# LCD_BOARD.net
KiCad netlist of a schematic drawn in EAGLE
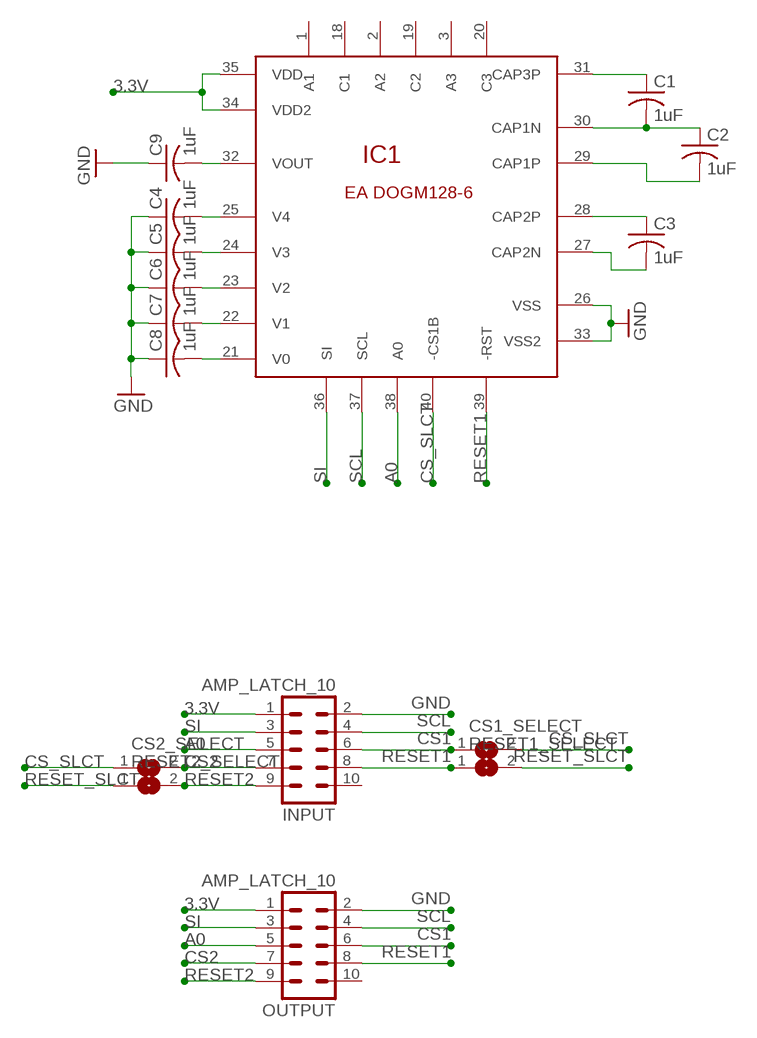
[diagram p0: schematic, sheet 1]

(export (version "E")
  (design (tool "Eeschema 10.0.6"))
  (components
    (comp (ref "C1")
      (value "1uF")
      (footprint "eagle-import:C1206")
      (libsource (lib "eagle-import") (part "C-USC1206"))
    )
    (comp (ref "C2")
      (value "1uF")
      (footprint "eagle-import:C1206")
      (libsource (lib "eagle-import") (part "C-USC1206"))
    )
    (comp (ref "C3")
      (value "1uF")
      (footprint "eagle-import:C1206")
      (libsource (lib "eagle-import") (part "C-USC1206"))
    )
    (comp (ref "C4")
      (value "1uF")
      (footprint "eagle-import:C1206")
      (libsource (lib "eagle-import") (part "C-USC1206"))
    )
    (comp (ref "C5")
      (value "1uF")
      (footprint "eagle-import:C1206")
      (libsource (lib "eagle-import") (part "C-USC1206"))
    )
    (comp (ref "C6")
      (value "1uF")
      (footprint "eagle-import:C1206")
      (libsource (lib "eagle-import") (part "C-USC1206"))
    )
    (comp (ref "C7")
      (value "1uF")
      (footprint "eagle-import:C1206")
      (libsource (lib "eagle-import") (part "C-USC1206"))
    )
    (comp (ref "C8")
      (value "1uF")
      (footprint "eagle-import:C1206")
      (libsource (lib "eagle-import") (part "C-USC1206"))
    )
    (comp (ref "C9")
      (value "1uF")
      (footprint "eagle-import:C1206")
      (libsource (lib "eagle-import") (part "C-USC1206"))
    )
    (comp (ref "CS1_SELECT")
      (value "SJ")
      (footprint "eagle-import:SJ")
      (libsource (lib "eagle-import") (part "SJ"))
    )
    (comp (ref "CS2_SELECT")
      (value "SJ")
      (footprint "eagle-import:SJ")
      (libsource (lib "eagle-import") (part "SJ"))
    )
    (comp (ref "IC1")
      (value "EADOGM128")
      (footprint "eagle-import:EADOGM128")
      (libsource (lib "eagle-import") (part "EADOGM128"))
    )
    (comp (ref "INPUT")
      (value "AMP_LATCH_10")
      (footprint "eagle-import:MA05-2")
      (fields (field (name "PART_NUM") "5499922-1"))
      (libsource (lib "eagle-import") (part "AMP_LATCH_10"))
    )
    (comp (ref "OUTPUT")
      (value "AMP_LATCH_10")
      (footprint "eagle-import:MA05-2")
      (fields (field (name "PART_NUM") "5499922-1"))
      (libsource (lib "eagle-import") (part "AMP_LATCH_10"))
    )
    (comp (ref "RESET1_SELECT")
      (value "SJ")
      (footprint "eagle-import:SJ")
      (libsource (lib "eagle-import") (part "SJ"))
    )
    (comp (ref "RESET2_SELECT")
      (value "SJ")
      (footprint "eagle-import:SJ")
      (libsource (lib "eagle-import") (part "SJ"))
    )
  )
  (nets
    (net (code "1") (name "/3.3V") (class "Default")
      (node (ref "IC1") (pin "34") (pinfunction "VDD2_34") (pintype "power_in"))
      (node (ref "IC1") (pin "35") (pinfunction "VDD_35") (pintype "power_in"))
      (node (ref "INPUT") (pin "1") (pinfunction "1_1") (pintype "passive"))
      (node (ref "OUTPUT") (pin "1") (pinfunction "1_1") (pintype "passive"))
    )
    (net (code "2") (name "/A0") (class "Default")
      (node (ref "IC1") (pin "38") (pinfunction "A0_38") (pintype "input"))
      (node (ref "INPUT") (pin "5") (pinfunction "5_5") (pintype "passive"))
      (node (ref "OUTPUT") (pin "5") (pinfunction "5_5") (pintype "passive"))
    )
    (net (code "3") (name "/CS1") (class "Default")
      (node (ref "CS1_SELECT") (pin "1") (pinfunction "1_1") (pintype "passive"))
      (node (ref "INPUT") (pin "6") (pinfunction "6_6") (pintype "passive"))
      (node (ref "OUTPUT") (pin "6") (pinfunction "6_6") (pintype "passive"))
    )
    (net (code "4") (name "/CS2") (class "Default")
      (node (ref "CS2_SELECT") (pin "2") (pinfunction "2_2") (pintype "passive"))
      (node (ref "INPUT") (pin "7") (pinfunction "7_7") (pintype "passive"))
      (node (ref "OUTPUT") (pin "7") (pinfunction "7_7") (pintype "passive"))
    )
    (net (code "5") (name "/CS_SLCT") (class "Default")
      (node (ref "CS1_SELECT") (pin "2") (pinfunction "2_2") (pintype "passive"))
      (node (ref "CS2_SELECT") (pin "1") (pinfunction "1_1") (pintype "passive"))
      (node (ref "IC1") (pin "40") (pinfunction "-CS1B_40") (pintype "input"))
    )
    (net (code "6") (name "/RESET1") (class "Default")
      (node (ref "IC1") (pin "39") (pinfunction "-RST_39") (pintype "input"))
      (node (ref "INPUT") (pin "8") (pinfunction "8_8") (pintype "passive"))
      (node (ref "OUTPUT") (pin "8") (pinfunction "8_8") (pintype "passive"))
      (node (ref "RESET1_SELECT") (pin "1") (pinfunction "1_1") (pintype "passive"))
    )
    (net (code "7") (name "/RESET2") (class "Default")
      (node (ref "INPUT") (pin "9") (pinfunction "9_9") (pintype "passive"))
      (node (ref "OUTPUT") (pin "9") (pinfunction "9_9") (pintype "passive"))
      (node (ref "RESET2_SELECT") (pin "2") (pinfunction "2_2") (pintype "passive"))
    )
    (net (code "8") (name "/RESET_SLCT") (class "Default")
      (node (ref "RESET1_SELECT") (pin "2") (pinfunction "2_2") (pintype "passive"))
      (node (ref "RESET2_SELECT") (pin "1") (pinfunction "1_1") (pintype "passive"))
    )
    (net (code "9") (name "/SCL") (class "Default")
      (node (ref "IC1") (pin "37") (pinfunction "SCL_37") (pintype "input"))
      (node (ref "INPUT") (pin "4") (pinfunction "4_4") (pintype "passive"))
      (node (ref "OUTPUT") (pin "4") (pinfunction "4_4") (pintype "passive"))
    )
    (net (code "10") (name "/SI") (class "Default")
      (node (ref "IC1") (pin "36") (pinfunction "SI_36") (pintype "input"))
      (node (ref "INPUT") (pin "3") (pinfunction "3_3") (pintype "passive"))
      (node (ref "OUTPUT") (pin "3") (pinfunction "3_3") (pintype "passive"))
    )
    (net (code "11") (name "GND") (class "Default")
      (node (ref "C4") (pin "1") (pinfunction "1_1") (pintype "passive"))
      (node (ref "C5") (pin "1") (pinfunction "1_1") (pintype "passive"))
      (node (ref "C6") (pin "1") (pinfunction "1_1") (pintype "passive"))
      (node (ref "C7") (pin "1") (pinfunction "1_1") (pintype "passive"))
      (node (ref "C8") (pin "1") (pinfunction "1_1") (pintype "passive"))
      (node (ref "C9") (pin "1") (pinfunction "1_1") (pintype "passive"))
      (node (ref "IC1") (pin "26") (pinfunction "VSS_26") (pintype "power_in"))
      (node (ref "IC1") (pin "33") (pinfunction "VSS2_33") (pintype "power_in"))
      (node (ref "INPUT") (pin "2") (pinfunction "2_2") (pintype "passive"))
      (node (ref "OUTPUT") (pin "2") (pinfunction "2_2") (pintype "passive"))
    )
    (net (code "12") (name "Net-(IC1-CAP1N)") (class "Default")
      (node (ref "C1") (pin "2") (pinfunction "2_2") (pintype "passive"))
      (node (ref "C2") (pin "1") (pinfunction "1_1") (pintype "passive"))
      (node (ref "IC1") (pin "30") (pinfunction "CAP1N_30") (pintype "passive"))
    )
    (net (code "13") (name "Net-(IC1-CAP1P)") (class "Default")
      (node (ref "C2") (pin "2") (pinfunction "2_2") (pintype "passive"))
      (node (ref "IC1") (pin "29") (pinfunction "CAP1P_29") (pintype "passive"))
    )
    (net (code "14") (name "Net-(IC1-CAP2N)") (class "Default")
      (node (ref "C3") (pin "2") (pinfunction "2_2") (pintype "passive"))
      (node (ref "IC1") (pin "27") (pinfunction "CAP2N_27") (pintype "passive"))
    )
    (net (code "15") (name "Net-(IC1-CAP2P)") (class "Default")
      (node (ref "C3") (pin "1") (pinfunction "1_1") (pintype "passive"))
      (node (ref "IC1") (pin "28") (pinfunction "CAP2P_28") (pintype "passive"))
    )
    (net (code "16") (name "Net-(IC1-CAP3P)") (class "Default")
      (node (ref "C1") (pin "1") (pinfunction "1_1") (pintype "passive"))
      (node (ref "IC1") (pin "31") (pinfunction "CAP3P_31") (pintype "passive"))
    )
    (net (code "17") (name "Net-(IC1-V0)") (class "Default")
      (node (ref "C8") (pin "2") (pinfunction "2_2") (pintype "passive"))
      (node (ref "IC1") (pin "21") (pinfunction "V0_21") (pintype "passive"))
    )
    (net (code "18") (name "Net-(IC1-V1)") (class "Default")
      (node (ref "C7") (pin "2") (pinfunction "2_2") (pintype "passive"))
      (node (ref "IC1") (pin "22") (pinfunction "V1_22") (pintype "passive"))
    )
    (net (code "19") (name "Net-(IC1-V2)") (class "Default")
      (node (ref "C6") (pin "2") (pinfunction "2_2") (pintype "passive"))
      (node (ref "IC1") (pin "23") (pinfunction "V2_23") (pintype "passive"))
    )
    (net (code "20") (name "Net-(IC1-V3)") (class "Default")
      (node (ref "C5") (pin "2") (pinfunction "2_2") (pintype "passive"))
      (node (ref "IC1") (pin "24") (pinfunction "V3_24") (pintype "passive"))
    )
    (net (code "21") (name "Net-(IC1-V4)") (class "Default")
      (node (ref "C4") (pin "2") (pinfunction "2_2") (pintype "passive"))
      (node (ref "IC1") (pin "25") (pinfunction "V4_25") (pintype "passive"))
    )
    (net (code "22") (name "Net-(IC1-VOUT)") (class "Default")
      (node (ref "C9") (pin "2") (pinfunction "2_2") (pintype "passive"))
      (node (ref "IC1") (pin "32") (pinfunction "VOUT_32") (pintype "passive"))
    )
    (net (code "23") (name "unconnected-(IC1-A1-Pad1)") (class "Default")
      (node (ref "IC1") (pin "1") (pinfunction "A1_1") (pintype "passive"))
    )
    (net (code "24") (name "unconnected-(IC1-A2-Pad2)") (class "Default")
      (node (ref "IC1") (pin "2") (pinfunction "A2_2") (pintype "passive"))
    )
    (net (code "25") (name "unconnected-(IC1-A3-Pad3)") (class "Default")
      (node (ref "IC1") (pin "3") (pinfunction "A3_3") (pintype "passive"))
    )
    (net (code "26") (name "unconnected-(IC1-C1-Pad18)") (class "Default")
      (node (ref "IC1") (pin "18") (pinfunction "C1_18") (pintype "passive"))
    )
    (net (code "27") (name "unconnected-(IC1-C2-Pad19)") (class "Default")
      (node (ref "IC1") (pin "19") (pinfunction "C2_19") (pintype "passive"))
    )
    (net (code "28") (name "unconnected-(IC1-C3-Pad20)") (class "Default")
      (node (ref "IC1") (pin "20") (pinfunction "C3_20") (pintype "passive"))
    )
    (net (code "29") (name "unconnected-(INPUT-Pad10)") (class "Default")
      (node (ref "INPUT") (pin "10") (pinfunction "10_10") (pintype "passive"))
    )
    (net (code "30") (name "unconnected-(OUTPUT-Pad10)") (class "Default")
      (node (ref "OUTPUT") (pin "10") (pinfunction "10_10") (pintype "passive"))
    )
  )
)
